# cronometroArduino.net
KiCad netlist of a schematic drawn in Altium Designer
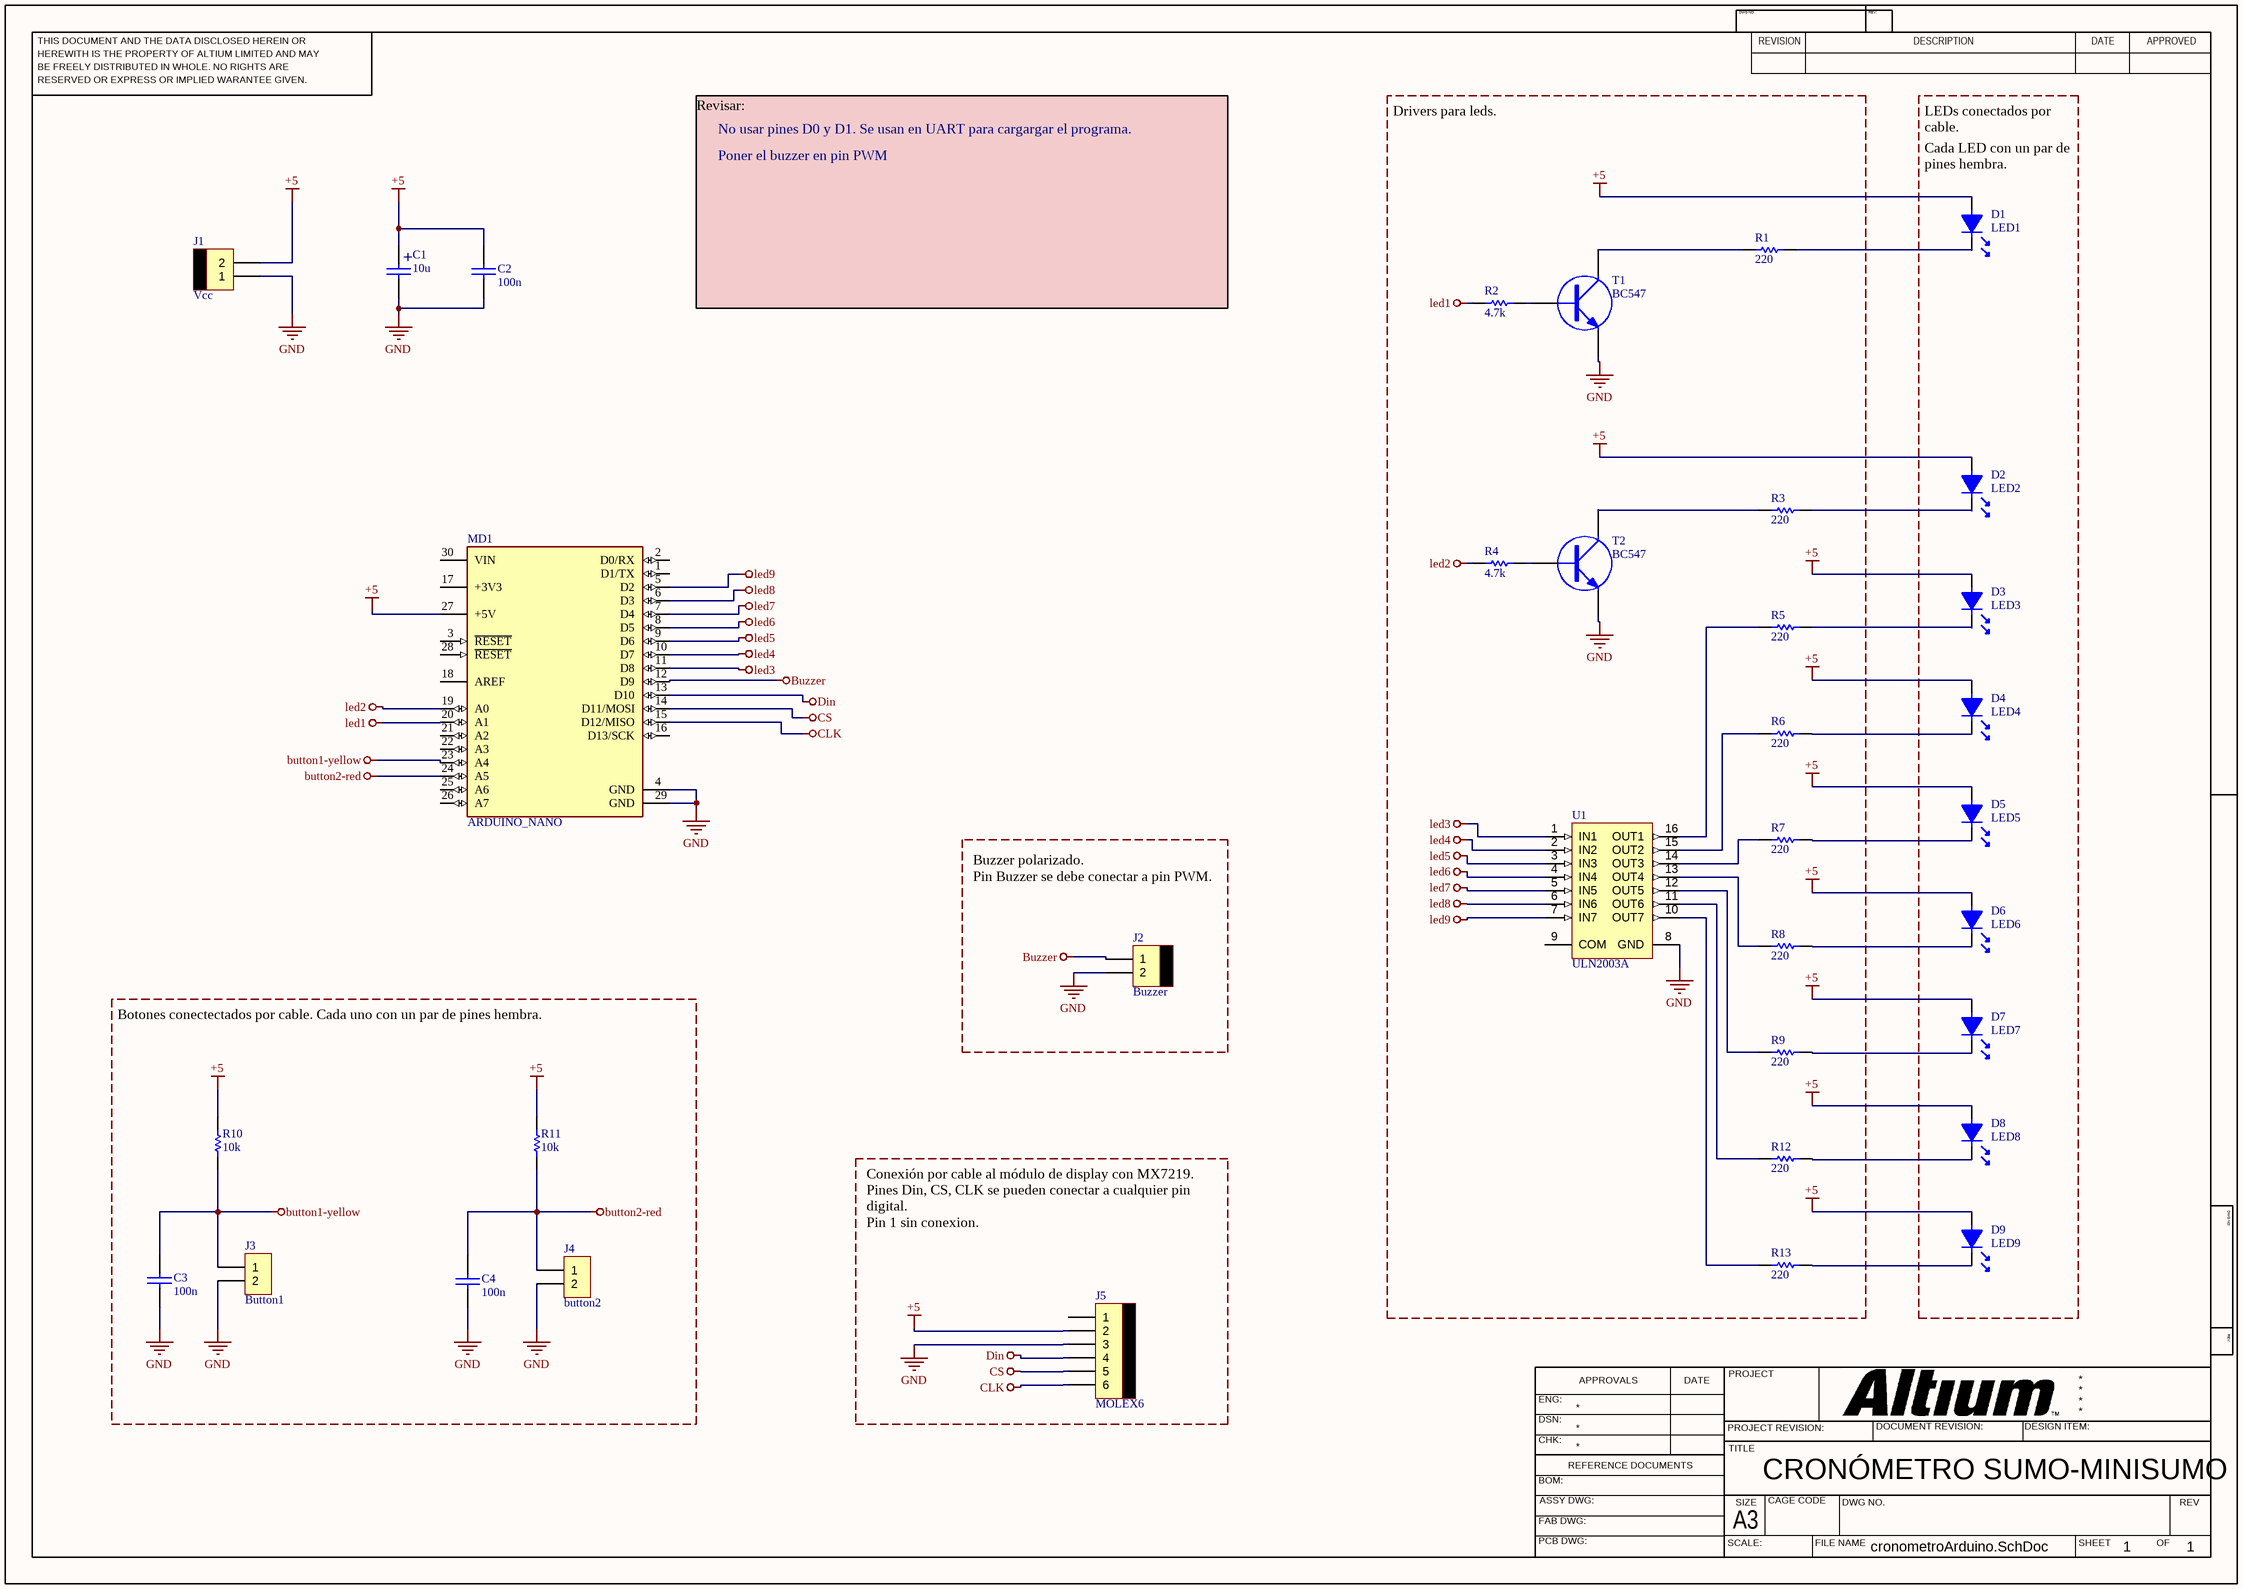
[diagram p0: cronometroArduino.SchDoc]

(export (version "E")
  (design (tool "Eeschema 10.0.6"))
  (components
    (comp (ref "C1") (value "10u") (footprint "CAP100RP") (libsource (lib "LIBEBAL") (part "CAPPOL")))
    (comp (ref "C2") (value "100n") (footprint "CAP200") (libsource (lib "LIBEBAL") (part "CAP")))
    (comp (ref "C3") (value "100n") (footprint "0805") (libsource (lib "LIBEBAL") (part "CAP")))
    (comp (ref "C4") (value "100n") (footprint "0805") (libsource (lib "LIBEBAL") (part "CAP")))
    (comp (ref "D1") (value "LED1") (footprint "LED3") (libsource (lib "LIBEBAL") (part "LED")))
    (comp (ref "D2") (value "LED2") (footprint "LED3") (libsource (lib "LIBEBAL") (part "LED")))
    (comp (ref "D3") (value "LED3") (footprint "LED3") (libsource (lib "LIBEBAL") (part "LED")))
    (comp (ref "D4") (value "LED4") (footprint "LED3") (libsource (lib "LIBEBAL") (part "LED")))
    (comp (ref "D5") (value "LED5") (footprint "LED3") (libsource (lib "LIBEBAL") (part "LED")))
    (comp (ref "D6") (value "LED6") (footprint "LED3") (libsource (lib "LIBEBAL") (part "LED")))
    (comp (ref "D7") (value "LED7") (footprint "LED3") (libsource (lib "LIBEBAL") (part "LED")))
    (comp (ref "D8") (value "LED8") (footprint "LED3") (libsource (lib "LIBEBAL") (part "LED")))
    (comp (ref "D9") (value "LED9") (footprint "LED3") (libsource (lib "LIBEBAL") (part "LED")))
    (comp (ref "J1")
      (value "Vcc")
      (footprint "MOLEX2")
      (description "Tensión de alimentación")
      (libsource (lib "") (part "MOLEX2_1"))
    )
    (comp (ref "J2") (value "Buzzer") (footprint "MOLEX2") (libsource (lib "LIBEBAL") (part "MOLEX2")))
    (comp (ref "J3") (value "Button1") (footprint "SIP2") (libsource (lib "LIBEBAL") (part "CON2")))
    (comp (ref "J4") (value "button2") (footprint "SIP2") (libsource (lib "LIBEBAL") (part "CON2")))
    (comp (ref "J5") (value "MOLEX6") (footprint "MOLEX6") (libsource (lib "LIBEBAL") (part "MOLEX6")))
    (comp (ref "MD1")
      (value "ARDUINO_NANO")
      (footprint "FP-A000005-MFG")
      (description "ARDUINO NANO ATMEGA328 EVAL BRD")
      (libsource (lib "Altium Content Vault") (part "d190c066e99afd1c6882cf92e11b2cc"))
    )
    (comp (ref "R1") (value "220") (footprint "RES400") (libsource (lib "LIBEBAL") (part "RES")))
    (comp (ref "R2") (value "4.7k") (footprint "0805") (libsource (lib "LIBEBAL") (part "RES")))
    (comp (ref "R3") (value "220") (footprint "RES400") (libsource (lib "LIBEBAL") (part "RES")))
    (comp (ref "R4") (value "4.7k") (footprint "0805") (libsource (lib "LIBEBAL") (part "RES")))
    (comp (ref "R5") (value "220") (footprint "RES400") (libsource (lib "LIBEBAL") (part "RES")))
    (comp (ref "R6") (value "220") (footprint "RES400") (libsource (lib "LIBEBAL") (part "RES")))
    (comp (ref "R7") (value "220") (footprint "RES400") (libsource (lib "LIBEBAL") (part "RES")))
    (comp (ref "R8") (value "220") (footprint "RES400") (libsource (lib "LIBEBAL") (part "RES")))
    (comp (ref "R9") (value "220") (footprint "RES400") (libsource (lib "LIBEBAL") (part "RES")))
    (comp (ref "R10") (value "10k") (footprint "0805") (libsource (lib "LIBEBAL") (part "RES")))
    (comp (ref "R11") (value "10k") (footprint "0805") (libsource (lib "LIBEBAL") (part "RES")))
    (comp (ref "R12") (value "220") (footprint "RES400") (libsource (lib "LIBEBAL") (part "RES")))
    (comp (ref "R13") (value "220") (footprint "RES400") (libsource (lib "LIBEBAL") (part "RES")))
    (comp (ref "T1") (value "BC547") (footprint "TO92") (libsource (lib "LIBEBAL") (part "TRANSISTOR NPN")))
    (comp (ref "T2") (value "BC547") (footprint "TO92") (libsource (lib "LIBEBAL") (part "TRANSISTOR NPN")))
    (comp (ref "U1")
      (value "ULN2003A")
      (footprint "STM-DIP-16L")
      (description "Seven Darlington Array, 50 V, 0.5 A, -40 to 85 degC, 16-Pin DIP, RoHS, Tube")
      (fields (field (name "MANUFACTURER") "STMicroelectronics"))
      (libsource (lib "Altium Content Vault") (part "STM-ULN2003A-PDIP-16"))
    )
  )
  (nets
    (net (code "1") (name "+5") (class "Default")
      (node (ref "C1") (pin "1") (pinfunction "1_1") (pintype "passive"))
      (node (ref "C2") (pin "1") (pinfunction "1_1") (pintype "passive"))
      (node (ref "D1") (pin "1") (pinfunction "1_1") (pintype "passive"))
      (node (ref "D2") (pin "1") (pinfunction "1_1") (pintype "passive"))
      (node (ref "D3") (pin "1") (pinfunction "1_1") (pintype "passive"))
      (node (ref "D4") (pin "1") (pinfunction "1_1") (pintype "passive"))
      (node (ref "D5") (pin "1") (pinfunction "1_1") (pintype "passive"))
      (node (ref "D6") (pin "1") (pinfunction "1_1") (pintype "passive"))
      (node (ref "D7") (pin "1") (pinfunction "1_1") (pintype "passive"))
      (node (ref "D8") (pin "1") (pinfunction "1_1") (pintype "passive"))
      (node (ref "D9") (pin "1") (pinfunction "1_1") (pintype "passive"))
      (node (ref "J1") (pin "2") (pinfunction "2_2") (pintype "passive"))
      (node (ref "J5") (pin "2") (pinfunction "2_2") (pintype "passive"))
      (node (ref "MD1") (pin "27") (pinfunction "+5V_27") (pintype "power_in"))
      (node (ref "R10") (pin "1") (pinfunction "1_1") (pintype "passive"))
      (node (ref "R11") (pin "1") (pinfunction "1_1") (pintype "passive"))
    )
    (net (code "2") (name "Buzzer") (class "Default")
      (node (ref "J2") (pin "1") (pinfunction "1_1") (pintype "passive"))
      (node (ref "MD1") (pin "12") (pinfunction "D9_12") (pintype "bidirectional"))
    )
    (net (code "3") (name "CLK") (class "Default")
      (node (ref "J5") (pin "6") (pinfunction "6_6") (pintype "passive"))
      (node (ref "MD1") (pin "15") (pinfunction "D12/MISO_15") (pintype "bidirectional"))
    )
    (net (code "4") (name "CS") (class "Default")
      (node (ref "J5") (pin "5") (pinfunction "5_5") (pintype "passive"))
      (node (ref "MD1") (pin "14") (pinfunction "D11/MOSI_14") (pintype "bidirectional"))
    )
    (net (code "5") (name "Din") (class "Default")
      (node (ref "J5") (pin "4") (pinfunction "4_4") (pintype "passive"))
      (node (ref "MD1") (pin "13") (pinfunction "D10_13") (pintype "bidirectional"))
    )
    (net (code "6") (name "GND") (class "Default")
      (node (ref "C1") (pin "2") (pinfunction "2_2") (pintype "passive"))
      (node (ref "C2") (pin "2") (pinfunction "2_2") (pintype "passive"))
      (node (ref "C3") (pin "2") (pinfunction "2_2") (pintype "passive"))
      (node (ref "C4") (pin "2") (pinfunction "2_2") (pintype "passive"))
      (node (ref "J1") (pin "1") (pinfunction "1_1") (pintype "passive"))
      (node (ref "J2") (pin "2") (pinfunction "2_2") (pintype "passive"))
      (node (ref "J3") (pin "2") (pinfunction "2_2") (pintype "passive"))
      (node (ref "J4") (pin "2") (pinfunction "2_2") (pintype "passive"))
      (node (ref "J5") (pin "3") (pinfunction "3_3") (pintype "passive"))
      (node (ref "MD1") (pin "29") (pinfunction "GND_29") (pintype "power_in"))
      (node (ref "MD1") (pin "4") (pinfunction "GND_4") (pintype "power_in"))
      (node (ref "T1") (pin "3") (pinfunction "E_3") (pintype "passive"))
      (node (ref "T2") (pin "3") (pinfunction "E_3") (pintype "passive"))
      (node (ref "U1") (pin "8") (pinfunction "GND_8") (pintype "power_in"))
    )
    (net (code "7") (name "Net-(D1-Pad2)") (class "Default")
      (node (ref "D1") (pin "2") (pinfunction "2_2") (pintype "passive"))
      (node (ref "R1") (pin "2") (pinfunction "2_2") (pintype "passive"))
    )
    (net (code "8") (name "Net-(D2-Pad2)") (class "Default")
      (node (ref "D2") (pin "2") (pinfunction "2_2") (pintype "passive"))
      (node (ref "R3") (pin "2") (pinfunction "2_2") (pintype "passive"))
    )
    (net (code "9") (name "Net-(D3-Pad2)") (class "Default")
      (node (ref "D3") (pin "2") (pinfunction "2_2") (pintype "passive"))
      (node (ref "R5") (pin "2") (pinfunction "2_2") (pintype "passive"))
    )
    (net (code "10") (name "Net-(D4-Pad2)") (class "Default")
      (node (ref "D4") (pin "2") (pinfunction "2_2") (pintype "passive"))
      (node (ref "R6") (pin "2") (pinfunction "2_2") (pintype "passive"))
    )
    (net (code "11") (name "Net-(D5-Pad2)") (class "Default")
      (node (ref "D5") (pin "2") (pinfunction "2_2") (pintype "passive"))
      (node (ref "R7") (pin "2") (pinfunction "2_2") (pintype "passive"))
    )
    (net (code "12") (name "Net-(D6-Pad2)") (class "Default")
      (node (ref "D6") (pin "2") (pinfunction "2_2") (pintype "passive"))
      (node (ref "R8") (pin "2") (pinfunction "2_2") (pintype "passive"))
    )
    (net (code "13") (name "Net-(D7-Pad2)") (class "Default")
      (node (ref "D7") (pin "2") (pinfunction "2_2") (pintype "passive"))
      (node (ref "R9") (pin "2") (pinfunction "2_2") (pintype "passive"))
    )
    (net (code "14") (name "Net-(D8-Pad2)") (class "Default")
      (node (ref "D8") (pin "2") (pinfunction "2_2") (pintype "passive"))
      (node (ref "R12") (pin "2") (pinfunction "2_2") (pintype "passive"))
    )
    (net (code "15") (name "Net-(D9-Pad2)") (class "Default")
      (node (ref "D9") (pin "2") (pinfunction "2_2") (pintype "passive"))
      (node (ref "R13") (pin "2") (pinfunction "2_2") (pintype "passive"))
    )
    (net (code "16") (name "Net-(T1-B)") (class "Default")
      (node (ref "R2") (pin "2") (pinfunction "2_2") (pintype "passive"))
      (node (ref "T1") (pin "1") (pinfunction "B_1") (pintype "passive"))
    )
    (net (code "17") (name "Net-(T1-C)") (class "Default")
      (node (ref "R1") (pin "1") (pinfunction "1_1") (pintype "passive"))
      (node (ref "T1") (pin "2") (pinfunction "C_2") (pintype "passive"))
    )
    (net (code "18") (name "Net-(T2-B)") (class "Default")
      (node (ref "R4") (pin "2") (pinfunction "2_2") (pintype "passive"))
      (node (ref "T2") (pin "1") (pinfunction "B_1") (pintype "passive"))
    )
    (net (code "19") (name "Net-(T2-C)") (class "Default")
      (node (ref "R3") (pin "1") (pinfunction "1_1") (pintype "passive"))
      (node (ref "T2") (pin "2") (pinfunction "C_2") (pintype "passive"))
    )
    (net (code "20") (name "Net-(U1-OUT1)") (class "Default")
      (node (ref "R5") (pin "1") (pinfunction "1_1") (pintype "passive"))
      (node (ref "U1") (pin "16") (pinfunction "OUT1_16") (pintype "output"))
    )
    (net (code "21") (name "Net-(U1-OUT2)") (class "Default")
      (node (ref "R6") (pin "1") (pinfunction "1_1") (pintype "passive"))
      (node (ref "U1") (pin "15") (pinfunction "OUT2_15") (pintype "output"))
    )
    (net (code "22") (name "Net-(U1-OUT3)") (class "Default")
      (node (ref "R7") (pin "1") (pinfunction "1_1") (pintype "passive"))
      (node (ref "U1") (pin "14") (pinfunction "OUT3_14") (pintype "output"))
    )
    (net (code "23") (name "Net-(U1-OUT4)") (class "Default")
      (node (ref "R8") (pin "1") (pinfunction "1_1") (pintype "passive"))
      (node (ref "U1") (pin "13") (pinfunction "OUT4_13") (pintype "output"))
    )
    (net (code "24") (name "Net-(U1-OUT5)") (class "Default")
      (node (ref "R9") (pin "1") (pinfunction "1_1") (pintype "passive"))
      (node (ref "U1") (pin "12") (pinfunction "OUT5_12") (pintype "output"))
    )
    (net (code "25") (name "Net-(U1-OUT6)") (class "Default")
      (node (ref "R12") (pin "1") (pinfunction "1_1") (pintype "passive"))
      (node (ref "U1") (pin "11") (pinfunction "OUT6_11") (pintype "output"))
    )
    (net (code "26") (name "Net-(U1-OUT7)") (class "Default")
      (node (ref "R13") (pin "1") (pinfunction "1_1") (pintype "passive"))
      (node (ref "U1") (pin "10") (pinfunction "OUT7_10") (pintype "output"))
    )
    (net (code "27") (name "button1-yellow") (class "Default")
      (node (ref "C3") (pin "1") (pinfunction "1_1") (pintype "passive"))
      (node (ref "J3") (pin "1") (pinfunction "1_1") (pintype "passive"))
      (node (ref "MD1") (pin "23") (pinfunction "A4_23") (pintype "bidirectional"))
      (node (ref "R10") (pin "2") (pinfunction "2_2") (pintype "passive"))
    )
    (net (code "28") (name "button2-red") (class "Default")
      (node (ref "C4") (pin "1") (pinfunction "1_1") (pintype "passive"))
      (node (ref "J4") (pin "1") (pinfunction "1_1") (pintype "passive"))
      (node (ref "MD1") (pin "24") (pinfunction "A5_24") (pintype "bidirectional"))
      (node (ref "R11") (pin "2") (pinfunction "2_2") (pintype "passive"))
    )
    (net (code "29") (name "led1") (class "Default")
      (node (ref "MD1") (pin "20") (pinfunction "A1_20") (pintype "bidirectional"))
      (node (ref "R2") (pin "1") (pinfunction "1_1") (pintype "passive"))
    )
    (net (code "30") (name "led2") (class "Default")
      (node (ref "MD1") (pin "19") (pinfunction "A0_19") (pintype "bidirectional"))
      (node (ref "R4") (pin "1") (pinfunction "1_1") (pintype "passive"))
    )
    (net (code "31") (name "led3") (class "Default")
      (node (ref "MD1") (pin "11") (pinfunction "D8_11") (pintype "bidirectional"))
      (node (ref "U1") (pin "1") (pinfunction "IN1_1") (pintype "input"))
    )
    (net (code "32") (name "led4") (class "Default")
      (node (ref "MD1") (pin "10") (pinfunction "D7_10") (pintype "bidirectional"))
      (node (ref "U1") (pin "2") (pinfunction "IN2_2") (pintype "input"))
    )
    (net (code "33") (name "led5") (class "Default")
      (node (ref "MD1") (pin "9") (pinfunction "D6_9") (pintype "bidirectional"))
      (node (ref "U1") (pin "3") (pinfunction "IN3_3") (pintype "input"))
    )
    (net (code "34") (name "led6") (class "Default")
      (node (ref "MD1") (pin "8") (pinfunction "D5_8") (pintype "bidirectional"))
      (node (ref "U1") (pin "4") (pinfunction "IN4_4") (pintype "input"))
    )
    (net (code "35") (name "led7") (class "Default")
      (node (ref "MD1") (pin "7") (pinfunction "D4_7") (pintype "bidirectional"))
      (node (ref "U1") (pin "5") (pinfunction "IN5_5") (pintype "input"))
    )
    (net (code "36") (name "led8") (class "Default")
      (node (ref "MD1") (pin "6") (pinfunction "D3_6") (pintype "bidirectional"))
      (node (ref "U1") (pin "6") (pinfunction "IN6_6") (pintype "input"))
    )
    (net (code "37") (name "led9") (class "Default")
      (node (ref "MD1") (pin "5") (pinfunction "D2_5") (pintype "bidirectional"))
      (node (ref "U1") (pin "7") (pinfunction "IN7_7") (pintype "input"))
    )
    (net (code "38") (name "unconnected-(J5-Pad1)") (class "Default")
      (node (ref "J5") (pin "1") (pinfunction "1_1") (pintype "passive"))
    )
    (net (code "39") (name "unconnected-(MD1-+3V3-Pad17)") (class "Default")
      (node (ref "MD1") (pin "17") (pinfunction "+3V3_17") (pintype "power_in"))
    )
    (net (code "40") (name "unconnected-(MD1-A2-Pad21)") (class "Default")
      (node (ref "MD1") (pin "21") (pinfunction "A2_21") (pintype "bidirectional"))
    )
    (net (code "41") (name "unconnected-(MD1-A3-Pad22)") (class "Default")
      (node (ref "MD1") (pin "22") (pinfunction "A3_22") (pintype "bidirectional"))
    )
    (net (code "42") (name "unconnected-(MD1-A6-Pad25)") (class "Default")
      (node (ref "MD1") (pin "25") (pinfunction "A6_25") (pintype "bidirectional"))
    )
    (net (code "43") (name "unconnected-(MD1-A7-Pad26)") (class "Default")
      (node (ref "MD1") (pin "26") (pinfunction "A7_26") (pintype "bidirectional"))
    )
    (net (code "44") (name "unconnected-(MD1-AREF-Pad18)") (class "Default")
      (node (ref "MD1") (pin "18") (pinfunction "AREF_18") (pintype "passive"))
    )
    (net (code "45") (name "unconnected-(MD1-D0{slash}RX-Pad2)") (class "Default")
      (node (ref "MD1") (pin "2") (pinfunction "D0/RX_2") (pintype "bidirectional"))
    )
    (net (code "46") (name "unconnected-(MD1-D1{slash}TX-Pad1)") (class "Default")
      (node (ref "MD1") (pin "1") (pinfunction "D1/TX_1") (pintype "bidirectional"))
    )
    (net (code "47") (name "unconnected-(MD1-D13{slash}SCK-Pad16)") (class "Default")
      (node (ref "MD1") (pin "16") (pinfunction "D13/SCK_16") (pintype "bidirectional"))
    )
    (net (code "48") (name "unconnected-(MD1-VIN-Pad30)") (class "Default")
      (node (ref "MD1") (pin "30") (pinfunction "VIN_30") (pintype "power_in"))
    )
    (net (code "49") (name "unconnected-(MD1-~{RESET}-Pad3)") (class "Default")
      (node (ref "MD1") (pin "3") (pinfunction "~{RESET}_3") (pintype "input"))
    )
    (net (code "50") (name "unconnected-(MD1-~{RESET}-Pad28)") (class "Default")
      (node (ref "MD1") (pin "28") (pinfunction "~{RESET}_28") (pintype "input"))
    )
    (net (code "51") (name "unconnected-(U1-COM-Pad9)") (class "Default")
      (node (ref "U1") (pin "9") (pinfunction "COM_9") (pintype "passive"))
    )
  )
)
